# DM3370_I2S_MICS.net
KiCad netlist of a schematic drawn in Altium Designer
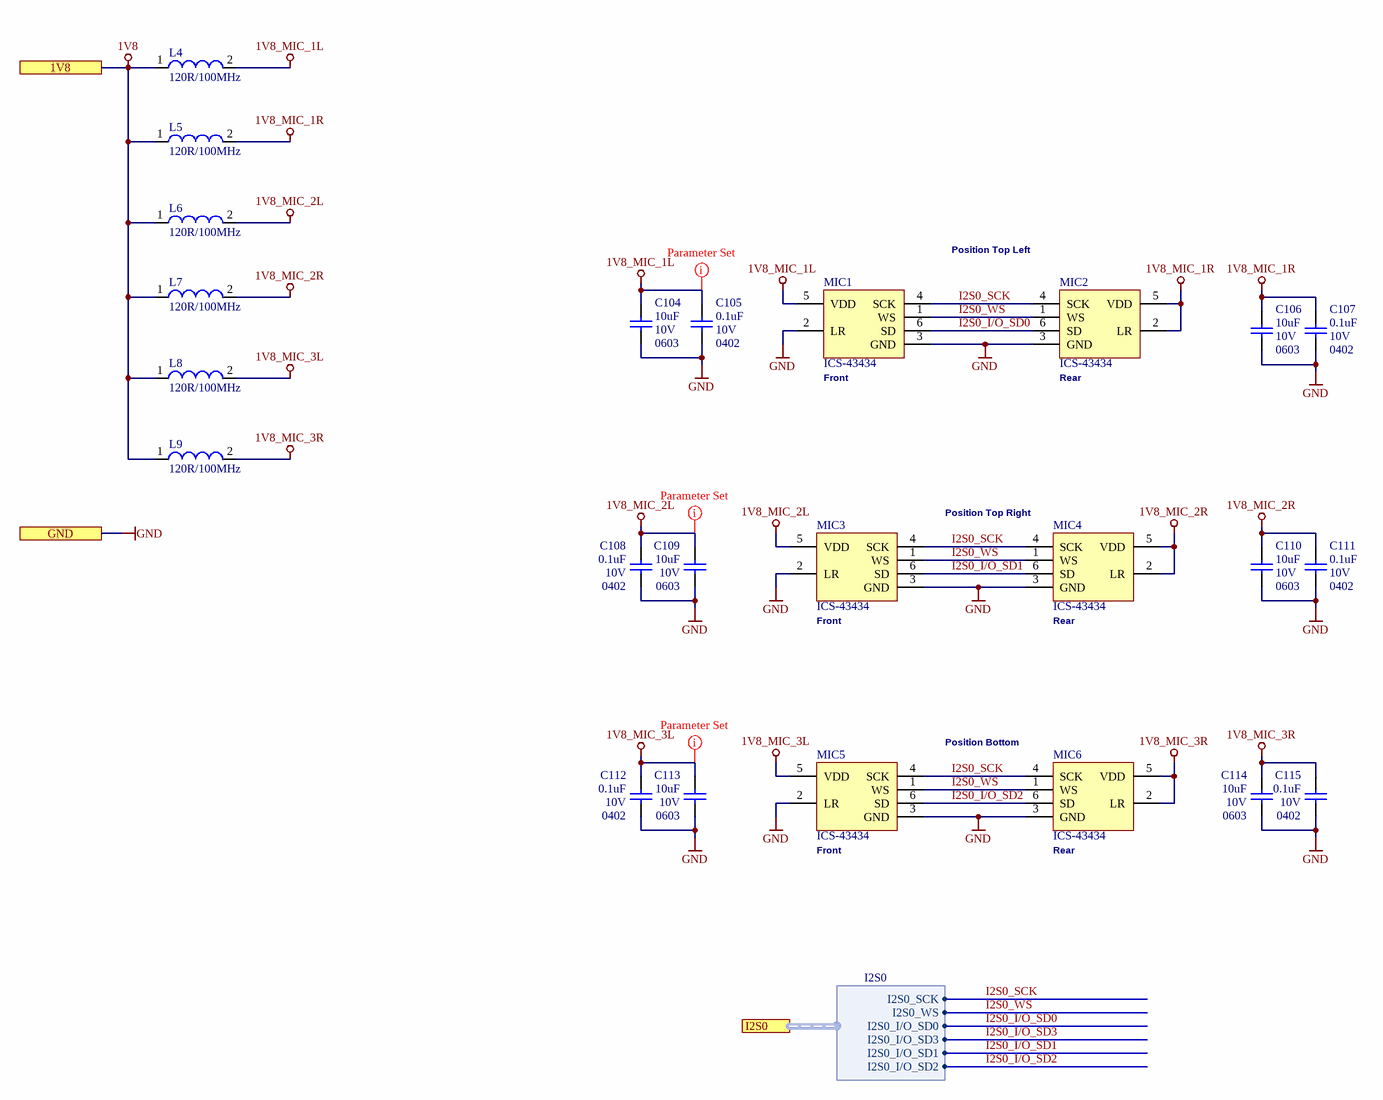
[diagram p0: DM3370_I2S_MICS.SchDoc]

(export (version "E")
  (design (tool "Eeschema 10.0.6"))
  (components
    (comp (ref "C104")
      (value "10uF 0603")
      (footprint "CAP_Altium_Vault_Generic:CAPC0603(1608)100_L")
      (description "CAP CER 10UF 10V X5R 0603 20%")
      (fields
        (field (name "CASE CODE (IMPERIAL)") "0603")
        (field (name "TOLERANCE") "20%")
        (field (name "CAPACITANCE") "10uF")
        (field (name "VOLTAGE RATING") "10V")
      )
      (libsource (lib "LuxonisMaster") (part "GRM188R61A106ME69D"))
    )
    (comp (ref "C105")
      (value "0.1uF 0402")
      (footprint "CAP_Altium_Vault_Generic:CAPC0402(1005)70_L")
      (description "CAP CER 0.1UF 10V X7R 0402 5%")
      (fields
        (field (name "CASE/PACKAGE") "0402")
        (field (name "CAPACITANCE") "0.1uF")
        (field (name "TOLERANCE") "5%")
        (field (name "VOLTAGE RATING") "10V")
      )
      (libsource (lib "LuxonisMaster") (part "GRM155R71A104JA01D"))
    )
    (comp (ref "C106")
      (value "10uF 0603")
      (footprint "CAP_Altium_Vault_Generic:CAPC0603(1608)100_L")
      (description "CAP CER 10UF 10V X5R 0603 20%")
      (fields
        (field (name "CASE CODE (IMPERIAL)") "0603")
        (field (name "TOLERANCE") "20%")
        (field (name "CAPACITANCE") "10uF")
        (field (name "VOLTAGE RATING") "10V")
      )
      (libsource (lib "LuxonisMaster") (part "GRM188R61A106ME69D"))
    )
    (comp (ref "C107")
      (value "0.1uF 0402")
      (footprint "CAP_Altium_Vault_Generic:CAPC0402(1005)70_L")
      (description "CAP CER 0.1UF 10V X7R 0402 5%")
      (fields
        (field (name "CASE/PACKAGE") "0402")
        (field (name "CAPACITANCE") "0.1uF")
        (field (name "TOLERANCE") "5%")
        (field (name "VOLTAGE RATING") "10V")
      )
      (libsource (lib "LuxonisMaster") (part "GRM155R71A104JA01D"))
    )
    (comp (ref "C108")
      (value "0.1uF 0402")
      (footprint "CAP_Altium_Vault_Generic:CAPC0402(1005)70_L")
      (description "CAP CER 0.1UF 10V X7R 0402 5%")
      (fields
        (field (name "CASE/PACKAGE") "0402")
        (field (name "CAPACITANCE") "0.1uF")
        (field (name "TOLERANCE") "5%")
        (field (name "VOLTAGE RATING") "10V")
      )
      (libsource (lib "LuxonisMaster") (part "GRM155R71A104JA01D"))
    )
    (comp (ref "C109")
      (value "10uF 0603")
      (footprint "CAP_Altium_Vault_Generic:CAPC0603(1608)100_L")
      (description "CAP CER 10UF 10V X5R 0603 20%")
      (fields
        (field (name "CASE CODE (IMPERIAL)") "0603")
        (field (name "TOLERANCE") "20%")
        (field (name "CAPACITANCE") "10uF")
        (field (name "VOLTAGE RATING") "10V")
      )
      (libsource (lib "LuxonisMaster") (part "GRM188R61A106ME69D"))
    )
    (comp (ref "C110")
      (value "10uF 0603")
      (footprint "CAP_Altium_Vault_Generic:CAPC0603(1608)100_L")
      (description "CAP CER 10UF 10V X5R 0603 20%")
      (fields
        (field (name "CASE CODE (IMPERIAL)") "0603")
        (field (name "TOLERANCE") "20%")
        (field (name "CAPACITANCE") "10uF")
        (field (name "VOLTAGE RATING") "10V")
      )
      (libsource (lib "LuxonisMaster") (part "GRM188R61A106ME69D"))
    )
    (comp (ref "C111")
      (value "0.1uF 0402")
      (footprint "CAP_Altium_Vault_Generic:CAPC0402(1005)70_L")
      (description "CAP CER 0.1UF 10V X7R 0402 5%")
      (fields
        (field (name "CASE/PACKAGE") "0402")
        (field (name "CAPACITANCE") "0.1uF")
        (field (name "TOLERANCE") "5%")
        (field (name "VOLTAGE RATING") "10V")
      )
      (libsource (lib "LuxonisMaster") (part "GRM155R71A104JA01D"))
    )
    (comp (ref "C112")
      (value "0.1uF 0402")
      (footprint "CAP_Altium_Vault_Generic:CAPC0402(1005)70_L")
      (description "CAP CER 0.1UF 10V X7R 0402 5%")
      (fields
        (field (name "CASE/PACKAGE") "0402")
        (field (name "CAPACITANCE") "0.1uF")
        (field (name "TOLERANCE") "5%")
        (field (name "VOLTAGE RATING") "10V")
      )
      (libsource (lib "LuxonisMaster") (part "GRM155R71A104JA01D"))
    )
    (comp (ref "C113")
      (value "10uF 0603")
      (footprint "CAP_Altium_Vault_Generic:CAPC0603(1608)100_L")
      (description "CAP CER 10UF 10V X5R 0603 20%")
      (fields
        (field (name "CASE CODE (IMPERIAL)") "0603")
        (field (name "TOLERANCE") "20%")
        (field (name "CAPACITANCE") "10uF")
        (field (name "VOLTAGE RATING") "10V")
      )
      (libsource (lib "LuxonisMaster") (part "GRM188R61A106ME69D"))
    )
    (comp (ref "C114")
      (value "10uF 0603")
      (footprint "CAP_Altium_Vault_Generic:CAPC0603(1608)100_L")
      (description "CAP CER 10UF 10V X5R 0603 20%")
      (fields
        (field (name "CASE CODE (IMPERIAL)") "0603")
        (field (name "TOLERANCE") "20%")
        (field (name "CAPACITANCE") "10uF")
        (field (name "VOLTAGE RATING") "10V")
      )
      (libsource (lib "LuxonisMaster") (part "GRM188R61A106ME69D"))
    )
    (comp (ref "C115")
      (value "0.1uF 0402")
      (footprint "CAP_Altium_Vault_Generic:CAPC0402(1005)70_L")
      (description "CAP CER 0.1UF 10V X7R 0402 5%")
      (fields
        (field (name "CASE/PACKAGE") "0402")
        (field (name "CAPACITANCE") "0.1uF")
        (field (name "TOLERANCE") "5%")
        (field (name "VOLTAGE RATING") "10V")
      )
      (libsource (lib "LuxonisMaster") (part "GRM155R71A104JA01D"))
    )
    (comp (ref "L4")
      (value "120R/100MHz")
      (footprint "LuxonisMaster:BLM18PG121SN1D_N")
      (description "FERRITE BEAD 120 OHM 0603 1LN")
      (fields (field (name "TOLERANCE") "25%"))
      (libsource (lib "LuxonisMaster") (part "BLM18PG121SN1D"))
    )
    (comp (ref "L5")
      (value "120R/100MHz")
      (footprint "LuxonisMaster:BLM18PG121SN1D_N")
      (description "FERRITE BEAD 120 OHM 0603 1LN")
      (fields (field (name "TOLERANCE") "25%"))
      (libsource (lib "LuxonisMaster") (part "BLM18PG121SN1D"))
    )
    (comp (ref "L6")
      (value "120R/100MHz")
      (footprint "LuxonisMaster:BLM18PG121SN1D_N")
      (description "FERRITE BEAD 120 OHM 0603 1LN")
      (fields (field (name "TOLERANCE") "25%"))
      (libsource (lib "LuxonisMaster") (part "BLM18PG121SN1D"))
    )
    (comp (ref "L7")
      (value "120R/100MHz")
      (footprint "LuxonisMaster:BLM18PG121SN1D_N")
      (description "FERRITE BEAD 120 OHM 0603 1LN")
      (fields (field (name "TOLERANCE") "25%"))
      (libsource (lib "LuxonisMaster") (part "BLM18PG121SN1D"))
    )
    (comp (ref "L8")
      (value "120R/100MHz")
      (footprint "LuxonisMaster:BLM18PG121SN1D_N")
      (description "FERRITE BEAD 120 OHM 0603 1LN")
      (fields (field (name "TOLERANCE") "25%"))
      (libsource (lib "LuxonisMaster") (part "BLM18PG121SN1D"))
    )
    (comp (ref "L9")
      (value "120R/100MHz")
      (footprint "LuxonisMaster:BLM18PG121SN1D_N")
      (description "FERRITE BEAD 120 OHM 0603 1LN")
      (fields (field (name "TOLERANCE") "25%"))
      (libsource (lib "LuxonisMaster") (part "BLM18PG121SN1D"))
    )
    (comp (ref "MIC1") (value "ICS-43434") (footprint "ICS-43434") (libsource (lib "") (part "ICS-43434_1")))
    (comp (ref "MIC2")
      (value "ICS-43434")
      (footprint "ICS-43434")
      (libsource (lib "Luxonis LLC") (part "ICS-43434"))
    )
    (comp (ref "MIC3") (value "ICS-43434") (footprint "ICS-43434") (libsource (lib "") (part "ICS-43434_1")))
    (comp (ref "MIC4")
      (value "ICS-43434")
      (footprint "ICS-43434")
      (libsource (lib "Luxonis LLC") (part "ICS-43434"))
    )
    (comp (ref "MIC5") (value "ICS-43434") (footprint "ICS-43434") (libsource (lib "") (part "ICS-43434_1")))
    (comp (ref "MIC6")
      (value "ICS-43434")
      (footprint "ICS-43434")
      (libsource (lib "Luxonis LLC") (part "ICS-43434"))
    )
  )
  (nets
    (net (code "2") (name "/I2S0_I{slash}O_SD0") (class "Default")
      (node (ref "MIC1") (pin "6") (pinfunction "SD_6") (pintype "passive"))
      (node (ref "MIC2") (pin "6") (pinfunction "SD_6") (pintype "passive"))
    )
    (net (code "3") (name "/I2S0_I{slash}O_SD1") (class "Default")
      (node (ref "MIC3") (pin "6") (pinfunction "SD_6") (pintype "passive"))
      (node (ref "MIC4") (pin "6") (pinfunction "SD_6") (pintype "passive"))
    )
    (net (code "4") (name "/I2S0_I{slash}O_SD2") (class "Default")
      (node (ref "MIC5") (pin "6") (pinfunction "SD_6") (pintype "passive"))
      (node (ref "MIC6") (pin "6") (pinfunction "SD_6") (pintype "passive"))
    )
    (net (code "6") (name "/I2S0_SCK") (class "Default")
      (node (ref "MIC1") (pin "4") (pinfunction "SCK_4") (pintype "passive"))
      (node (ref "MIC2") (pin "4") (pinfunction "SCK_4") (pintype "passive"))
      (node (ref "MIC3") (pin "4") (pinfunction "SCK_4") (pintype "passive"))
      (node (ref "MIC4") (pin "4") (pinfunction "SCK_4") (pintype "passive"))
      (node (ref "MIC5") (pin "4") (pinfunction "SCK_4") (pintype "passive"))
      (node (ref "MIC6") (pin "4") (pinfunction "SCK_4") (pintype "passive"))
    )
    (net (code "7") (name "/I2S0_WS") (class "Default")
      (node (ref "MIC1") (pin "1") (pinfunction "WS_1") (pintype "passive"))
      (node (ref "MIC2") (pin "1") (pinfunction "WS_1") (pintype "passive"))
      (node (ref "MIC3") (pin "1") (pinfunction "WS_1") (pintype "passive"))
      (node (ref "MIC4") (pin "1") (pinfunction "WS_1") (pintype "passive"))
      (node (ref "MIC5") (pin "1") (pinfunction "WS_1") (pintype "passive"))
      (node (ref "MIC6") (pin "1") (pinfunction "WS_1") (pintype "passive"))
    )
    (net (code "9") (name "1V8") (class "Default")
      (node (ref "L4") (pin "1") (pinfunction "1_1") (pintype "passive"))
      (node (ref "L5") (pin "1") (pinfunction "1_1") (pintype "passive"))
      (node (ref "L6") (pin "1") (pinfunction "1_1") (pintype "passive"))
      (node (ref "L7") (pin "1") (pinfunction "1_1") (pintype "passive"))
      (node (ref "L8") (pin "1") (pinfunction "1_1") (pintype "passive"))
      (node (ref "L9") (pin "1") (pinfunction "1_1") (pintype "passive"))
    )
    (net (code "10") (name "1V8_MIC_1L") (class "Default")
      (node (ref "C104") (pin "2") (pinfunction "2_2") (pintype "passive"))
      (node (ref "C105") (pin "2") (pinfunction "2_2") (pintype "passive"))
      (node (ref "L4") (pin "2") (pinfunction "2_2") (pintype "passive"))
      (node (ref "MIC1") (pin "5") (pinfunction "VDD_5") (pintype "passive"))
    )
    (net (code "11") (name "1V8_MIC_1R") (class "Default")
      (node (ref "C106") (pin "2") (pinfunction "2_2") (pintype "passive"))
      (node (ref "C107") (pin "2") (pinfunction "2_2") (pintype "passive"))
      (node (ref "L5") (pin "2") (pinfunction "2_2") (pintype "passive"))
      (node (ref "MIC2") (pin "2") (pinfunction "LR_2") (pintype "passive"))
      (node (ref "MIC2") (pin "5") (pinfunction "VDD_5") (pintype "passive"))
    )
    (net (code "12") (name "1V8_MIC_2L") (class "Default")
      (node (ref "C108") (pin "2") (pinfunction "2_2") (pintype "passive"))
      (node (ref "C109") (pin "2") (pinfunction "2_2") (pintype "passive"))
      (node (ref "L6") (pin "2") (pinfunction "2_2") (pintype "passive"))
      (node (ref "MIC3") (pin "5") (pinfunction "VDD_5") (pintype "passive"))
    )
    (net (code "13") (name "1V8_MIC_2R") (class "Default")
      (node (ref "C110") (pin "2") (pinfunction "2_2") (pintype "passive"))
      (node (ref "C111") (pin "2") (pinfunction "2_2") (pintype "passive"))
      (node (ref "L7") (pin "2") (pinfunction "2_2") (pintype "passive"))
      (node (ref "MIC4") (pin "2") (pinfunction "LR_2") (pintype "passive"))
      (node (ref "MIC4") (pin "5") (pinfunction "VDD_5") (pintype "passive"))
    )
    (net (code "14") (name "1V8_MIC_3L") (class "Default")
      (node (ref "C112") (pin "2") (pinfunction "2_2") (pintype "passive"))
      (node (ref "C113") (pin "2") (pinfunction "2_2") (pintype "passive"))
      (node (ref "L8") (pin "2") (pinfunction "2_2") (pintype "passive"))
      (node (ref "MIC5") (pin "5") (pinfunction "VDD_5") (pintype "passive"))
    )
    (net (code "15") (name "1V8_MIC_3R") (class "Default")
      (node (ref "C114") (pin "2") (pinfunction "2_2") (pintype "passive"))
      (node (ref "C115") (pin "2") (pinfunction "2_2") (pintype "passive"))
      (node (ref "L9") (pin "2") (pinfunction "2_2") (pintype "passive"))
      (node (ref "MIC6") (pin "2") (pinfunction "LR_2") (pintype "passive"))
      (node (ref "MIC6") (pin "5") (pinfunction "VDD_5") (pintype "passive"))
    )
    (net (code "16") (name "GND") (class "Default")
      (node (ref "C104") (pin "1") (pinfunction "1_1") (pintype "passive"))
      (node (ref "C105") (pin "1") (pinfunction "1_1") (pintype "passive"))
      (node (ref "C106") (pin "1") (pinfunction "1_1") (pintype "passive"))
      (node (ref "C107") (pin "1") (pinfunction "1_1") (pintype "passive"))
      (node (ref "C108") (pin "1") (pinfunction "1_1") (pintype "passive"))
      (node (ref "C109") (pin "1") (pinfunction "1_1") (pintype "passive"))
      (node (ref "C110") (pin "1") (pinfunction "1_1") (pintype "passive"))
      (node (ref "C111") (pin "1") (pinfunction "1_1") (pintype "passive"))
      (node (ref "C112") (pin "1") (pinfunction "1_1") (pintype "passive"))
      (node (ref "C113") (pin "1") (pinfunction "1_1") (pintype "passive"))
      (node (ref "C114") (pin "1") (pinfunction "1_1") (pintype "passive"))
      (node (ref "C115") (pin "1") (pinfunction "1_1") (pintype "passive"))
      (node (ref "MIC1") (pin "2") (pinfunction "LR_2") (pintype "passive"))
      (node (ref "MIC1") (pin "3") (pinfunction "GND_3") (pintype "passive"))
      (node (ref "MIC2") (pin "3") (pinfunction "GND_3") (pintype "passive"))
      (node (ref "MIC3") (pin "2") (pinfunction "LR_2") (pintype "passive"))
      (node (ref "MIC3") (pin "3") (pinfunction "GND_3") (pintype "passive"))
      (node (ref "MIC4") (pin "3") (pinfunction "GND_3") (pintype "passive"))
      (node (ref "MIC5") (pin "2") (pinfunction "LR_2") (pintype "passive"))
      (node (ref "MIC5") (pin "3") (pinfunction "GND_3") (pintype "passive"))
      (node (ref "MIC6") (pin "3") (pinfunction "GND_3") (pintype "passive"))
    )
  )
)
